# 7_MINIPCIE.net
KiCad netlist of a schematic drawn in Altium Designer
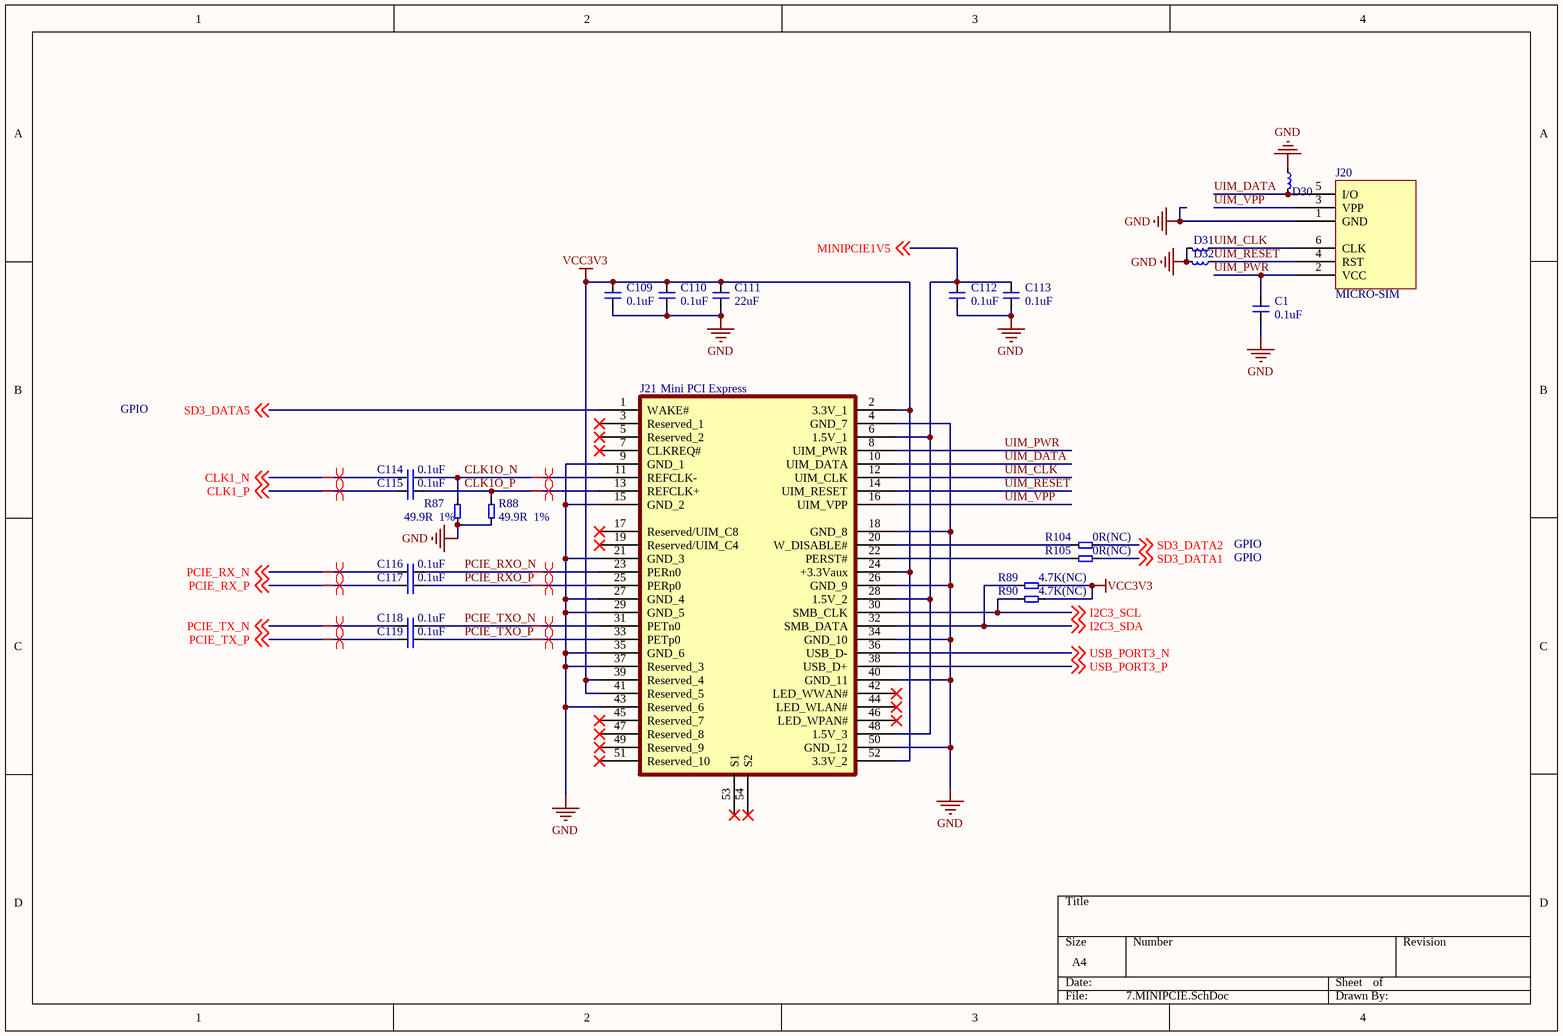
[diagram p0: 7.MINIPCIE.SchDoc]

(export (version "E")
  (design (tool "Eeschema 10.0.6"))
  (components
    (comp (ref "C1")
      (value "0.1uF")
      (footprint "0603C")
      (description "电容")
      (libsource (lib "LDT-SCH") (part "电容"))
    )
    (comp (ref "C109")
      (value "0.1uF")
      (footprint "0603C")
      (description "电容")
      (libsource (lib "LDT-SCH") (part "电容"))
    )
    (comp (ref "C110")
      (value "0.1uF")
      (footprint "0603C")
      (description "电容")
      (libsource (lib "LDT-SCH") (part "电容"))
    )
    (comp (ref "C111")
      (value "22uF")
      (footprint "0603C")
      (description "电容")
      (libsource (lib "LDT-SCH") (part "电容"))
    )
    (comp (ref "C112")
      (value "0.1uF")
      (footprint "0603C")
      (description "电容")
      (libsource (lib "LDT-SCH") (part "电容"))
    )
    (comp (ref "C113")
      (value "0.1uF")
      (footprint "0603C")
      (description "电容")
      (libsource (lib "LDT-SCH") (part "电容"))
    )
    (comp (ref "C114")
      (value "0.1uF")
      (footprint "0603C")
      (description "电容")
      (libsource (lib "LDT-SCH") (part "电容"))
    )
    (comp (ref "C115")
      (value "0.1uF")
      (footprint "0603C")
      (description "电容")
      (libsource (lib "LDT-SCH") (part "电容"))
    )
    (comp (ref "C116")
      (value "0.1uF")
      (footprint "0603C")
      (description "电容")
      (libsource (lib "LDT-SCH") (part "电容"))
    )
    (comp (ref "C117")
      (value "0.1uF")
      (footprint "0603C")
      (description "电容")
      (libsource (lib "LDT-SCH") (part "电容"))
    )
    (comp (ref "C118")
      (value "0.1uF")
      (footprint "0603C")
      (description "电容")
      (libsource (lib "LDT-SCH") (part "电容"))
    )
    (comp (ref "C119")
      (value "0.1uF")
      (footprint "0603C")
      (description "电容")
      (libsource (lib "LDT-SCH") (part "电容"))
    )
    (comp (ref "D30") (value "ESD") (footprint "0603L") (libsource (lib "LDT-SCH") (part "电感")))
    (comp (ref "D31") (value "ESD") (footprint "0603L") (libsource (lib "LDT-SCH") (part "电感")))
    (comp (ref "D32") (value "ESD") (footprint "0603L") (libsource (lib "LDT-SCH") (part "电感")))
    (comp (ref "J20")
      (value "MICRO-SIM")
      (footprint "MACRO-SIM")
      (libsource (lib "LDT-SCH") (part "MICRO-SIM"))
    )
    (comp (ref "J21")
      (value "Mini PCI Express")
      (footprint "MINI-PCIE")
      (description "MPC24-52K3311")
      (libsource (lib "LDT-SCH") (part "MINIPCIE"))
    )
    (comp (ref "R87")
      (value "49.9R  1%")
      (footprint "0603R")
      (description "电阻")
      (libsource (lib "LDT-SCH") (part "电阻"))
    )
    (comp (ref "R88")
      (value "49.9R  1%")
      (footprint "0603R")
      (description "电阻")
      (libsource (lib "LDT-SCH") (part "电阻"))
    )
    (comp (ref "R89")
      (value "4.7K(NC)")
      (footprint "0603R")
      (description "电阻")
      (libsource (lib "LDT-SCH") (part "电阻"))
    )
    (comp (ref "R90")
      (value "4.7K(NC)")
      (footprint "0603R")
      (description "电阻")
      (libsource (lib "LDT-SCH") (part "电阻"))
    )
    (comp (ref "R104")
      (value "0R(NC)")
      (footprint "0603R")
      (description "电阻")
      (libsource (lib "LDT-SCH") (part "电阻"))
    )
    (comp (ref "R105")
      (value "0R(NC)")
      (footprint "0603R")
      (description "电阻")
      (libsource (lib "LDT-SCH") (part "电阻"))
    )
  )
  (nets
    (net (code "1") (name "/CLK1O_N") (class "Default")
      (node (ref "C114") (pin "2") (pintype "passive"))
      (node (ref "J21") (pin "11") (pinfunction "REFCLK-_11") (pintype "passive"))
      (node (ref "R87") (pin "2") (pintype "passive"))
    )
    (net (code "2") (name "/CLK1O_P") (class "Default")
      (node (ref "C115") (pin "2") (pintype "passive"))
      (node (ref "J21") (pin "13") (pinfunction "REFCLK+_13") (pintype "passive"))
      (node (ref "R88") (pin "2") (pintype "passive"))
    )
    (net (code "3") (name "/PCIE_RXO_N") (class "Default")
      (node (ref "C116") (pin "2") (pintype "passive"))
      (node (ref "J21") (pin "23") (pinfunction "PERn0_23") (pintype "passive"))
    )
    (net (code "4") (name "/PCIE_RXO_P") (class "Default")
      (node (ref "C117") (pin "2") (pintype "passive"))
      (node (ref "J21") (pin "25") (pinfunction "PERp0_25") (pintype "passive"))
    )
    (net (code "5") (name "/PCIE_TXO_N") (class "Default")
      (node (ref "C118") (pin "2") (pintype "passive"))
      (node (ref "J21") (pin "31") (pinfunction "PETn0_31") (pintype "passive"))
    )
    (net (code "6") (name "/PCIE_TXO_P") (class "Default")
      (node (ref "C119") (pin "2") (pintype "passive"))
      (node (ref "J21") (pin "33") (pinfunction "PETp0_33") (pintype "passive"))
    )
    (net (code "7") (name "/UIM_CLK") (class "Default")
      (node (ref "D31") (pin "1") (pintype "passive"))
      (node (ref "J20") (pin "6") (pinfunction "CLK_6") (pintype "passive"))
      (node (ref "J21") (pin "12") (pinfunction "UIM_CLK_12") (pintype "passive"))
    )
    (net (code "8") (name "/UIM_DATA") (class "Default")
      (node (ref "D30") (pin "2") (pintype "passive"))
      (node (ref "J20") (pin "5") (pinfunction "I/O_5") (pintype "passive"))
      (node (ref "J21") (pin "10") (pinfunction "UIM_DATA_10") (pintype "passive"))
    )
    (net (code "9") (name "/UIM_PWR") (class "Default")
      (node (ref "C1") (pin "1") (pintype "passive"))
      (node (ref "J20") (pin "2") (pinfunction "VCC_2") (pintype "passive"))
      (node (ref "J21") (pin "8") (pinfunction "UIM_PWR_8") (pintype "passive"))
    )
    (net (code "10") (name "/UIM_RESET") (class "Default")
      (node (ref "D32") (pin "1") (pintype "passive"))
      (node (ref "J20") (pin "4") (pinfunction "RST_4") (pintype "passive"))
      (node (ref "J21") (pin "14") (pinfunction "UIM_RESET_14") (pintype "passive"))
    )
    (net (code "11") (name "/UIM_VPP") (class "Default")
      (node (ref "J20") (pin "3") (pinfunction "VPP_3") (pintype "passive"))
      (node (ref "J21") (pin "16") (pinfunction "UIM_VPP_16") (pintype "passive"))
    )
    (net (code "12") (name "CLK1_N") (class "Default") (node (ref "C114") (pin "1") (pintype "passive")))
    (net (code "13") (name "CLK1_P") (class "Default") (node (ref "C115") (pin "1") (pintype "passive")))
    (net (code "14") (name "GND") (class "Default")
      (node (ref "C1") (pin "2") (pintype "passive"))
      (node (ref "C109") (pin "2") (pintype "passive"))
      (node (ref "C110") (pin "2") (pintype "passive"))
      (node (ref "C111") (pin "2") (pintype "passive"))
      (node (ref "C112") (pin "2") (pintype "passive"))
      (node (ref "C113") (pin "2") (pintype "passive"))
      (node (ref "D30") (pin "1") (pintype "passive"))
      (node (ref "D31") (pin "2") (pintype "passive"))
      (node (ref "D32") (pin "2") (pintype "passive"))
      (node (ref "J20") (pin "1") (pinfunction "GND_1") (pintype "passive"))
      (node (ref "J21") (pin "15") (pinfunction "GND_2_15") (pintype "passive"))
      (node (ref "J21") (pin "18") (pinfunction "GND_8_18") (pintype "passive"))
      (node (ref "J21") (pin "21") (pinfunction "GND_3_21") (pintype "passive"))
      (node (ref "J21") (pin "26") (pinfunction "GND_9_26") (pintype "passive"))
      (node (ref "J21") (pin "27") (pinfunction "GND_4_27") (pintype "passive"))
      (node (ref "J21") (pin "29") (pinfunction "GND_5_29") (pintype "passive"))
      (node (ref "J21") (pin "34") (pinfunction "GND_10_34") (pintype "passive"))
      (node (ref "J21") (pin "35") (pinfunction "GND_6_35") (pintype "passive"))
      (node (ref "J21") (pin "37") (pinfunction "Reserved_3_37") (pintype "passive"))
      (node (ref "J21") (pin "4") (pinfunction "GND_7_4") (pintype "passive"))
      (node (ref "J21") (pin "40") (pinfunction "GND_11_40") (pintype "passive"))
      (node (ref "J21") (pin "43") (pinfunction "Reserved_6_43") (pintype "passive"))
      (node (ref "J21") (pin "50") (pinfunction "GND_12_50") (pintype "passive"))
      (node (ref "J21") (pin "9") (pinfunction "GND_1_9") (pintype "passive"))
      (node (ref "R87") (pin "1") (pintype "passive"))
      (node (ref "R88") (pin "1") (pintype "passive"))
    )
    (net (code "15") (name "I2C3_SCL") (class "Default")
      (node (ref "J21") (pin "30") (pinfunction "SMB_CLK_30") (pintype "passive"))
      (node (ref "R90") (pin "2") (pintype "passive"))
    )
    (net (code "16") (name "I2C3_SDA") (class "Default")
      (node (ref "J21") (pin "32") (pinfunction "SMB_DATA_32") (pintype "passive"))
      (node (ref "R89") (pin "2") (pintype "passive"))
    )
    (net (code "17") (name "MINIPCIE1V5") (class "Default")
      (node (ref "C112") (pin "1") (pintype "passive"))
      (node (ref "C113") (pin "1") (pintype "passive"))
      (node (ref "J21") (pin "28") (pinfunction "1.5V_2_28") (pintype "passive"))
      (node (ref "J21") (pin "48") (pinfunction "1.5V_3_48") (pintype "passive"))
      (node (ref "J21") (pin "6") (pinfunction "1.5V_1_6") (pintype "passive"))
    )
    (net (code "18") (name "Net-(J21-PERST#)") (class "Default")
      (node (ref "J21") (pin "22") (pinfunction "PERST#_22") (pintype "passive"))
      (node (ref "R105") (pin "2") (pintype "passive"))
    )
    (net (code "19") (name "Net-(J21-W_DISABLE#)") (class "Default")
      (node (ref "J21") (pin "20") (pinfunction "W_DISABLE#_20") (pintype "passive"))
      (node (ref "R104") (pin "2") (pintype "passive"))
    )
    (net (code "20") (name "PCIE_RX_N") (class "Default") (node (ref "C116") (pin "1") (pintype "passive")))
    (net (code "21") (name "PCIE_RX_P") (class "Default") (node (ref "C117") (pin "1") (pintype "passive")))
    (net (code "22") (name "PCIE_TX_N") (class "Default") (node (ref "C118") (pin "1") (pintype "passive")))
    (net (code "23") (name "PCIE_TX_P") (class "Default") (node (ref "C119") (pin "1") (pintype "passive")))
    (net (code "24") (name "SD3_DATA1") (class "Default") (node (ref "R105") (pin "1") (pintype "passive")))
    (net (code "25") (name "SD3_DATA2") (class "Default") (node (ref "R104") (pin "1") (pintype "passive")))
    (net (code "26") (name "SD3_DATA5") (class "Default")
      (node (ref "J21") (pin "1") (pinfunction "WAKE#_1") (pintype "passive"))
    )
    (net (code "27") (name "USB_PORT3_N") (class "Default")
      (node (ref "J21") (pin "36") (pinfunction "USB_D-_36") (pintype "passive"))
    )
    (net (code "28") (name "USB_PORT3_P") (class "Default")
      (node (ref "J21") (pin "38") (pinfunction "USB_D+_38") (pintype "passive"))
    )
    (net (code "29") (name "VCC3V3") (class "Default")
      (node (ref "C109") (pin "1") (pintype "passive"))
      (node (ref "C110") (pin "1") (pintype "passive"))
      (node (ref "C111") (pin "1") (pintype "passive"))
      (node (ref "J21") (pin "2") (pinfunction "3.3V_1_2") (pintype "passive"))
      (node (ref "J21") (pin "24") (pinfunction "+3.3Vaux_24") (pintype "passive"))
      (node (ref "J21") (pin "39") (pinfunction "Reserved_4_39") (pintype "passive"))
      (node (ref "J21") (pin "41") (pinfunction "Reserved_5_41") (pintype "passive"))
      (node (ref "J21") (pin "52") (pinfunction "3.3V_2_52") (pintype "passive"))
      (node (ref "R89") (pin "1") (pintype "passive"))
      (node (ref "R90") (pin "1") (pintype "passive"))
    )
    (net (code "30") (name "unconnected-(J21-CLKREQ#-Pad7)") (class "Default")
      (node (ref "J21") (pin "7") (pinfunction "CLKREQ#_7") (pintype "passive+no_connect"))
    )
    (net (code "31") (name "unconnected-(J21-LED_WLAN#-Pad44)") (class "Default")
      (node (ref "J21") (pin "44") (pinfunction "LED_WLAN#_44") (pintype "passive+no_connect"))
    )
    (net (code "32") (name "unconnected-(J21-LED_WPAN#-Pad46)") (class "Default")
      (node (ref "J21") (pin "46") (pinfunction "LED_WPAN#_46") (pintype "passive+no_connect"))
    )
    (net (code "33") (name "unconnected-(J21-LED_WWAN#-Pad42)") (class "Default")
      (node (ref "J21") (pin "42") (pinfunction "LED_WWAN#_42") (pintype "passive+no_connect"))
    )
    (net (code "34") (name "unconnected-(J21-Reserved_1-Pad3)") (class "Default")
      (node (ref "J21") (pin "3") (pinfunction "Reserved_1_3") (pintype "passive+no_connect"))
    )
    (net (code "35") (name "unconnected-(J21-Reserved_2-Pad5)") (class "Default")
      (node (ref "J21") (pin "5") (pinfunction "Reserved_2_5") (pintype "passive+no_connect"))
    )
    (net (code "36") (name "unconnected-(J21-Reserved_7-Pad45)") (class "Default")
      (node (ref "J21") (pin "45") (pinfunction "Reserved_7_45") (pintype "passive+no_connect"))
    )
    (net (code "37") (name "unconnected-(J21-Reserved_8-Pad47)") (class "Default")
      (node (ref "J21") (pin "47") (pinfunction "Reserved_8_47") (pintype "passive+no_connect"))
    )
    (net (code "38") (name "unconnected-(J21-Reserved_9-Pad49)") (class "Default")
      (node (ref "J21") (pin "49") (pinfunction "Reserved_9_49") (pintype "passive+no_connect"))
    )
    (net (code "39") (name "unconnected-(J21-Reserved_10-Pad51)") (class "Default")
      (node (ref "J21") (pin "51") (pinfunction "Reserved_10_51") (pintype "passive+no_connect"))
    )
    (net (code "40") (name "unconnected-(J21-Reserved{slash}UIM_C4-Pad19)") (class "Default")
      (node (ref "J21") (pin "19") (pinfunction "Reserved/UIM_C4_19") (pintype "passive+no_connect"))
    )
    (net (code "41") (name "unconnected-(J21-Reserved{slash}UIM_C8-Pad17)") (class "Default")
      (node (ref "J21") (pin "17") (pinfunction "Reserved/UIM_C8_17") (pintype "passive+no_connect"))
    )
    (net (code "42") (name "unconnected-(J21-S1-Pad53)") (class "Default")
      (node (ref "J21") (pin "53") (pinfunction "S1_53") (pintype "passive+no_connect"))
    )
    (net (code "43") (name "unconnected-(J21-S2-Pad54)") (class "Default")
      (node (ref "J21") (pin "54") (pinfunction "S2_54") (pintype "passive+no_connect"))
    )
  )
)
